# REF_Base.net
KiCad netlist of a schematic drawn in EasyEDA Pro
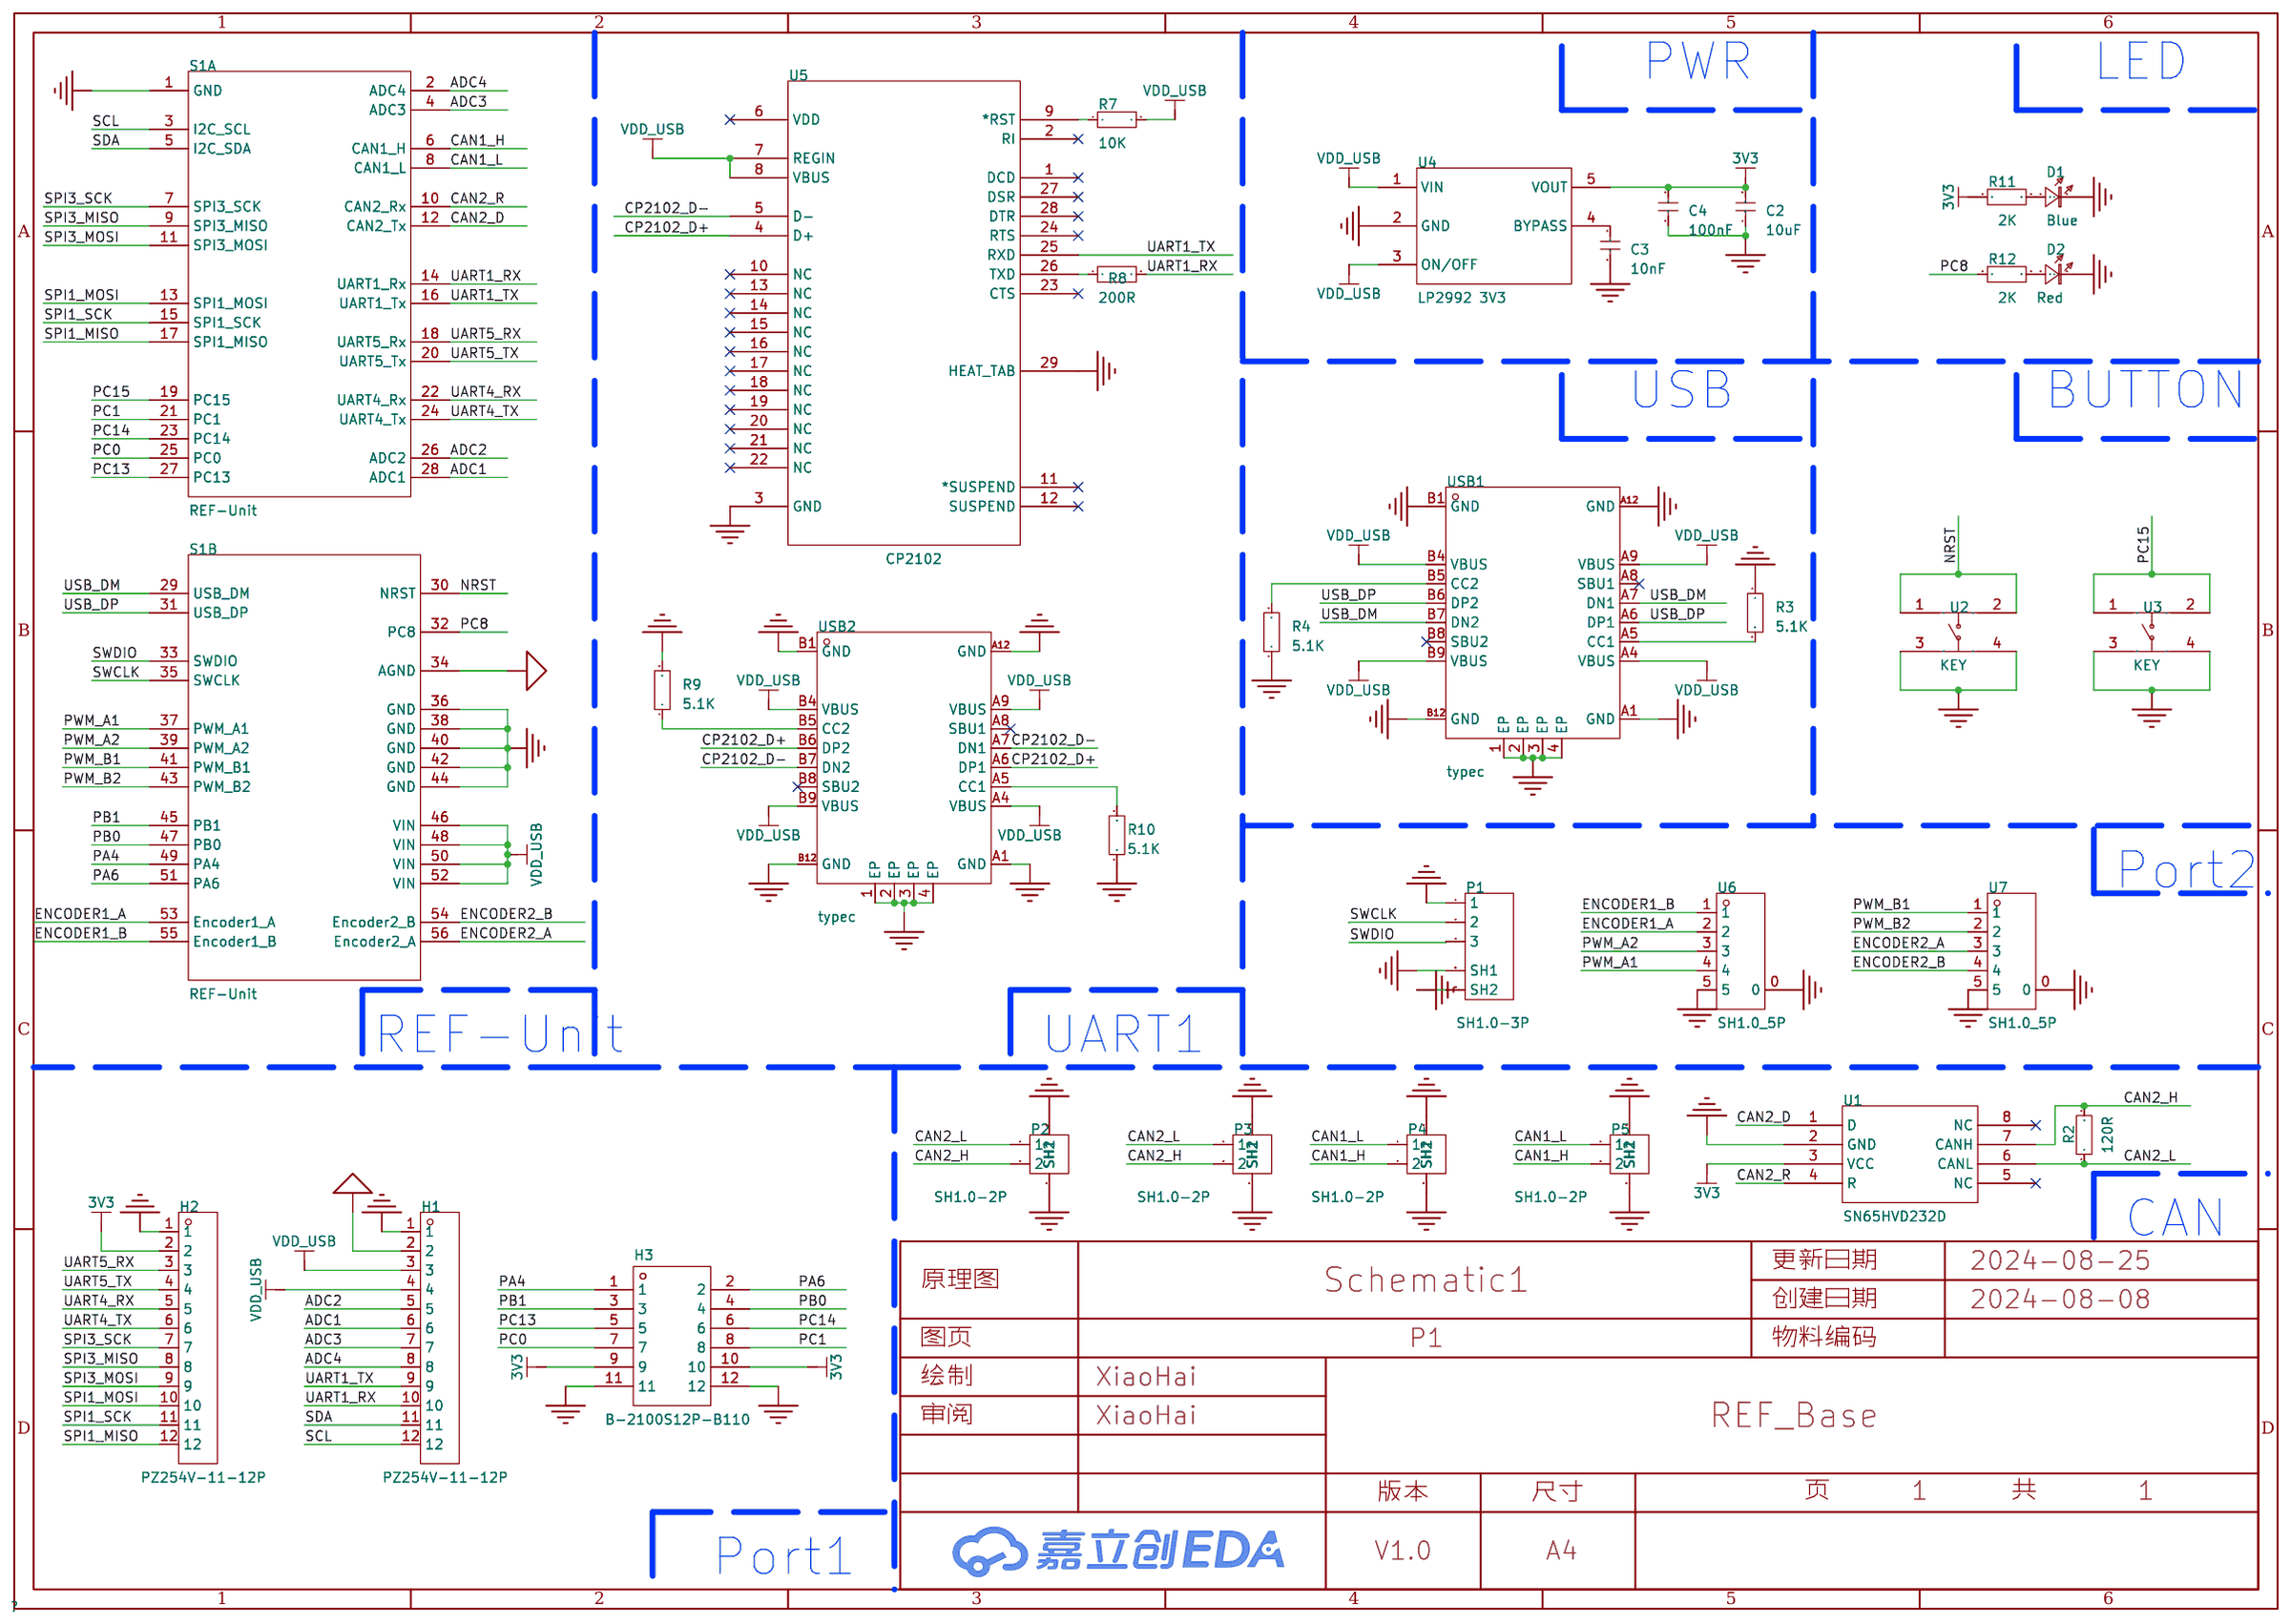
[diagram p0: schematic sheet]

(export (version "E")
  (design (tool "Eeschema 10.0.6"))
  (components
    (comp (ref "C2")
      (value "0.1u")
      (footprint "easyedapro:CAP_0402")
      (libsource (lib "easyedapro") (part "电容-0402"))
    )
    (comp (ref "C3")
      (value "0.1u")
      (footprint "easyedapro:CAP_0402")
      (libsource (lib "easyedapro") (part "电容-0402"))
    )
    (comp (ref "C4")
      (value "0.1u")
      (footprint "easyedapro:CAP_0402")
      (libsource (lib "easyedapro") (part "电容-0402"))
    )
    (comp (ref "D1")
      (value "color?")
      (footprint "easyedapro:LED_0402_RED")
      (libsource (lib "easyedapro") (part "LED_0402"))
    )
    (comp (ref "D2")
      (value "color?")
      (footprint "easyedapro:LED_0402_RED")
      (libsource (lib "easyedapro") (part "LED_0402"))
    )
    (comp (ref "H1")
      (value "PZ254V-11-12P")
      (footprint "easyedapro:HDR-TH_12P-P2.54-V-M")
      (fields (field (name "Manufacturer") "XFCN(兴飞)"))
      (libsource (lib "easyedapro") (part "PZ254V-11-12P"))
    )
    (comp (ref "H2")
      (value "PZ254V-11-12P")
      (footprint "easyedapro:HDR-TH_12P-P2.54-V-M")
      (fields (field (name "Manufacturer") "XFCN(兴飞)"))
      (libsource (lib "easyedapro") (part "PZ254V-11-12P"))
    )
    (comp (ref "H3")
      (value "B-2100S12P-B110")
      (footprint "easyedapro:HDR-TH_12P-P2.54-V-M-R2-C6-S2.54")
      (fields (field (name "Manufacturer") "Ckmtw(灿科盟)"))
      (libsource (lib "easyedapro") (part "210S-2*6P L=11.6MMGold-plated black"))
    )
    (comp (ref "P1")
      (value "SH1.0-3P")
      (footprint "easyedapro:SH1.0-3P")
      (libsource (lib "easyedapro") (part "SH1.0-3P"))
    )
    (comp (ref "P2")
      (value "SH1.0-2P")
      (footprint "easyedapro:SH1.0-2P")
      (libsource (lib "easyedapro") (part "SH1.0-2P"))
    )
    (comp (ref "P3")
      (value "SH1.0-2P")
      (footprint "easyedapro:SH1.0-2P")
      (libsource (lib "easyedapro") (part "SH1.0-2P"))
    )
    (comp (ref "P4")
      (value "SH1.0-2P")
      (footprint "easyedapro:SH1.0-2P")
      (libsource (lib "easyedapro") (part "SH1.0-2P"))
    )
    (comp (ref "P5")
      (value "SH1.0-2P")
      (footprint "easyedapro:SH1.0-2P")
      (libsource (lib "easyedapro") (part "SH1.0-2P"))
    )
    (comp (ref "R2")
      (value "22R")
      (footprint "easyedapro:RES_0402")
      (libsource (lib "easyedapro") (part "电阻-0402"))
    )
    (comp (ref "R3")
      (value "22R")
      (footprint "easyedapro:RES_0402")
      (libsource (lib "easyedapro") (part "电阻-0402"))
    )
    (comp (ref "R4")
      (value "22R")
      (footprint "easyedapro:RES_0402")
      (libsource (lib "easyedapro") (part "电阻-0402"))
    )
    (comp (ref "R7")
      (value "22R")
      (footprint "easyedapro:RES_0402")
      (libsource (lib "easyedapro") (part "电阻-0402"))
    )
    (comp (ref "R8")
      (value "22R")
      (footprint "easyedapro:RES_0402")
      (libsource (lib "easyedapro") (part "电阻-0402"))
    )
    (comp (ref "R9")
      (value "22R")
      (footprint "easyedapro:RES_0402")
      (libsource (lib "easyedapro") (part "电阻-0402"))
    )
    (comp (ref "R10")
      (value "22R")
      (footprint "easyedapro:RES_0402")
      (libsource (lib "easyedapro") (part "电阻-0402"))
    )
    (comp (ref "R11")
      (value "22R")
      (footprint "easyedapro:RES_0402")
      (libsource (lib "easyedapro") (part "电阻-0402"))
    )
    (comp (ref "R12")
      (value "22R")
      (footprint "easyedapro:RES_0402")
      (libsource (lib "easyedapro") (part "电阻-0402"))
    )
    (comp (ref "S1")
      (value "REF-Unit")
      (footprint "easyedapro:REF-UNIT")
      (libsource (lib "easyedapro") (part "REF-Unit"))
    )
    (comp (ref "U1")
      (value "SN65HVD232D")
      (footprint "easyedapro:SO-8")
      (fields (field (name "Manufacturer") "Texas Instruments"))
      (libsource (lib "easyedapro") (part "SN65HVD232D"))
    )
    (comp (ref "U2")
      (value "KEY")
      (footprint "easyedapro:KEY-SMD_TSC4A")
      (fields (field (name "Manufacturer") "SHOU HAN(首韩)"))
      (libsource (lib "easyedapro") (part "TSC4A 160GF-WZ 016"))
    )
    (comp (ref "U3")
      (value "KEY")
      (footprint "easyedapro:KEY-SMD_TSC4A")
      (fields (field (name "Manufacturer") "SHOU HAN(首韩)"))
      (libsource (lib "easyedapro") (part "TSC4A 160GF-WZ 016"))
    )
    (comp (ref "U4")
      (value "LP2992 3V3")
      (footprint "easyedapro:SOT23-5")
      (libsource (lib "easyedapro") (part "LP2992"))
    )
    (comp (ref "U5")
      (value "Value")
      (footprint "easyedapro:QFN-28")
      (libsource (lib "easyedapro") (part "CP2102"))
    )
    (comp (ref "U6")
      (value "SH1.0_5P")
      (footprint "easyedapro:CONN-SMD_5P-SH1.00-5P-WT")
      (libsource (lib "easyedapro") (part "SH1.0_5P"))
    )
    (comp (ref "U7")
      (value "SH1.0_5P")
      (footprint "easyedapro:CONN-SMD_5P-SH1.00-5P-WT")
      (libsource (lib "easyedapro") (part "SH1.0_5P"))
    )
    (comp (ref "USB1")
      (value "typec")
      (footprint "easyedapro:USB-C-SMD_KH-TYPE-C-16P")
      (libsource (lib "easyedapro") (part "TYPEC_C9900016956"))
    )
    (comp (ref "USB2")
      (value "typec")
      (footprint "easyedapro:USB-C-SMD_KH-TYPE-C-16P")
      (libsource (lib "easyedapro") (part "TYPEC_C9900016956"))
    )
  )
  (nets
    (net (code "1") (name "/ADC1") (class "Default")
      (node (ref "H1") (pin "6") (pinfunction "6_6") (pintype "unspecified"))
      (node (ref "S1") (pin "28") (pinfunction "ADC1_28") (pintype "input"))
    )
    (net (code "2") (name "/ADC2") (class "Default")
      (node (ref "H1") (pin "5") (pinfunction "5_5") (pintype "unspecified"))
      (node (ref "S1") (pin "26") (pinfunction "ADC2_26") (pintype "input"))
    )
    (net (code "3") (name "/ADC3") (class "Default")
      (node (ref "H1") (pin "7") (pinfunction "7_7") (pintype "unspecified"))
      (node (ref "S1") (pin "4") (pinfunction "ADC3_4") (pintype "input"))
    )
    (net (code "4") (name "/ADC4") (class "Default")
      (node (ref "H1") (pin "8") (pinfunction "8_8") (pintype "unspecified"))
      (node (ref "S1") (pin "2") (pinfunction "ADC4_2") (pintype "input"))
    )
    (net (code "5") (name "/CAN1_H") (class "Default")
      (node (ref "P4") (pin "2") (pinfunction "2_2") (pintype "unspecified"))
      (node (ref "P5") (pin "2") (pinfunction "2_2") (pintype "unspecified"))
      (node (ref "S1") (pin "6") (pinfunction "CAN1_H_6") (pintype "bidirectional"))
    )
    (net (code "6") (name "/CAN1_L") (class "Default")
      (node (ref "P4") (pin "1") (pinfunction "1_1") (pintype "unspecified"))
      (node (ref "P5") (pin "1") (pinfunction "1_1") (pintype "unspecified"))
      (node (ref "S1") (pin "8") (pinfunction "CAN1_L_8") (pintype "bidirectional"))
    )
    (net (code "7") (name "/CAN2_D") (class "Default")
      (node (ref "S1") (pin "12") (pinfunction "CAN2_Tx_12") (pintype "bidirectional"))
      (node (ref "U1") (pin "1") (pinfunction "D_1") (pintype "unspecified"))
    )
    (net (code "8") (name "/CAN2_H") (class "Default")
      (node (ref "P2") (pin "2") (pinfunction "2_2") (pintype "unspecified"))
      (node (ref "P3") (pin "2") (pinfunction "2_2") (pintype "unspecified"))
      (node (ref "R2") (pin "2") (pinfunction "2_2") (pintype "unspecified"))
      (node (ref "U1") (pin "7") (pinfunction "CANH_7") (pintype "unspecified"))
    )
    (net (code "9") (name "/CAN2_L") (class "Default")
      (node (ref "P2") (pin "1") (pinfunction "1_1") (pintype "unspecified"))
      (node (ref "P3") (pin "1") (pinfunction "1_1") (pintype "unspecified"))
      (node (ref "R2") (pin "1") (pinfunction "1_1") (pintype "unspecified"))
      (node (ref "U1") (pin "6") (pinfunction "CANL_6") (pintype "unspecified"))
    )
    (net (code "10") (name "/CAN2_R") (class "Default")
      (node (ref "S1") (pin "10") (pinfunction "CAN2_Rx_10") (pintype "bidirectional"))
      (node (ref "U1") (pin "4") (pinfunction "R_4") (pintype "unspecified"))
    )
    (net (code "11") (name "/CP2102_D+") (class "Default")
      (node (ref "U5") (pin "4") (pinfunction "D+_4") (pintype "unspecified"))
      (node (ref "USB2") (pin "A6") (pinfunction "DP1_A6") (pintype "unspecified"))
      (node (ref "USB2") (pin "B6") (pinfunction "DP2_B6") (pintype "unspecified"))
    )
    (net (code "12") (name "/CP2102_D-") (class "Default")
      (node (ref "U5") (pin "5") (pinfunction "D-_5") (pintype "unspecified"))
      (node (ref "USB2") (pin "A7") (pinfunction "DN1_A7") (pintype "unspecified"))
      (node (ref "USB2") (pin "B7") (pinfunction "DN2_B7") (pintype "unspecified"))
    )
    (net (code "13") (name "/ENCODER1_A") (class "Default")
      (node (ref "S1") (pin "53") (pinfunction "Encoder1_A_53") (pintype "input"))
      (node (ref "U6") (pin "2") (pinfunction "2_2") (pintype "unspecified"))
    )
    (net (code "14") (name "/ENCODER1_B") (class "Default")
      (node (ref "S1") (pin "55") (pinfunction "Encoder1_B_55") (pintype "input"))
      (node (ref "U6") (pin "1") (pinfunction "1_1") (pintype "unspecified"))
    )
    (net (code "15") (name "/ENCODER2_A") (class "Default")
      (node (ref "S1") (pin "56") (pinfunction "Encoder2_A_56") (pintype "input"))
      (node (ref "U7") (pin "3") (pinfunction "3_3") (pintype "unspecified"))
    )
    (net (code "16") (name "/ENCODER2_B") (class "Default")
      (node (ref "S1") (pin "54") (pinfunction "Encoder2_B_54") (pintype "input"))
      (node (ref "U7") (pin "4") (pinfunction "4_4") (pintype "unspecified"))
    )
    (net (code "17") (name "/NRST") (class "Default")
      (node (ref "S1") (pin "30") (pinfunction "NRST_30") (pintype "unspecified"))
      (node (ref "U2") (pin "1") (pinfunction "1_1") (pintype "unspecified"))
      (node (ref "U2") (pin "2") (pinfunction "2_2") (pintype "unspecified"))
    )
    (net (code "18") (name "/PA4") (class "Default")
      (node (ref "H3") (pin "1") (pinfunction "1_1") (pintype "unspecified"))
      (node (ref "S1") (pin "49") (pinfunction "PA4_49") (pintype "bidirectional"))
    )
    (net (code "19") (name "/PA6") (class "Default")
      (node (ref "H3") (pin "2") (pinfunction "2_2") (pintype "unspecified"))
      (node (ref "S1") (pin "51") (pinfunction "PA6_51") (pintype "bidirectional"))
    )
    (net (code "20") (name "/PB0") (class "Default")
      (node (ref "H3") (pin "4") (pinfunction "4_4") (pintype "unspecified"))
      (node (ref "S1") (pin "47") (pinfunction "PB0_47") (pintype "bidirectional"))
    )
    (net (code "21") (name "/PB1") (class "Default")
      (node (ref "H3") (pin "3") (pinfunction "3_3") (pintype "unspecified"))
      (node (ref "S1") (pin "45") (pinfunction "PB1_45") (pintype "bidirectional"))
    )
    (net (code "22") (name "/PC0") (class "Default")
      (node (ref "H3") (pin "7") (pinfunction "7_7") (pintype "unspecified"))
      (node (ref "S1") (pin "25") (pinfunction "PC0_25") (pintype "bidirectional"))
    )
    (net (code "23") (name "/PC1") (class "Default")
      (node (ref "H3") (pin "8") (pinfunction "8_8") (pintype "unspecified"))
      (node (ref "S1") (pin "21") (pinfunction "PC1_21") (pintype "bidirectional"))
    )
    (net (code "24") (name "/PC8") (class "Default")
      (node (ref "R12") (pin "1") (pinfunction "1_1") (pintype "unspecified"))
      (node (ref "S1") (pin "32") (pinfunction "PC8_32") (pintype "bidirectional"))
    )
    (net (code "25") (name "/PC13") (class "Default")
      (node (ref "H3") (pin "5") (pinfunction "5_5") (pintype "unspecified"))
      (node (ref "S1") (pin "27") (pinfunction "PC13_27") (pintype "bidirectional"))
    )
    (net (code "26") (name "/PC14") (class "Default")
      (node (ref "H3") (pin "6") (pinfunction "6_6") (pintype "unspecified"))
      (node (ref "S1") (pin "23") (pinfunction "PC14_23") (pintype "bidirectional"))
    )
    (net (code "27") (name "/PC15") (class "Default")
      (node (ref "S1") (pin "19") (pinfunction "PC15_19") (pintype "bidirectional"))
      (node (ref "U3") (pin "1") (pinfunction "1_1") (pintype "unspecified"))
      (node (ref "U3") (pin "2") (pinfunction "2_2") (pintype "unspecified"))
    )
    (net (code "28") (name "/PWM_A1") (class "Default")
      (node (ref "S1") (pin "37") (pinfunction "PWM_A1_37") (pintype "output"))
      (node (ref "U6") (pin "4") (pinfunction "4_4") (pintype "unspecified"))
    )
    (net (code "29") (name "/PWM_A2") (class "Default")
      (node (ref "S1") (pin "39") (pinfunction "PWM_A2_39") (pintype "output"))
      (node (ref "U6") (pin "3") (pinfunction "3_3") (pintype "unspecified"))
    )
    (net (code "30") (name "/PWM_B1") (class "Default")
      (node (ref "S1") (pin "41") (pinfunction "PWM_B1_41") (pintype "output"))
      (node (ref "U7") (pin "1") (pinfunction "1_1") (pintype "unspecified"))
    )
    (net (code "31") (name "/PWM_B2") (class "Default")
      (node (ref "S1") (pin "43") (pinfunction "PWM_B2_43") (pintype "output"))
      (node (ref "U7") (pin "2") (pinfunction "2_2") (pintype "unspecified"))
    )
    (net (code "32") (name "/SCL") (class "Default")
      (node (ref "H1") (pin "12") (pinfunction "12_12") (pintype "unspecified"))
      (node (ref "S1") (pin "3") (pinfunction "I2C_SCL_3") (pintype "bidirectional"))
    )
    (net (code "33") (name "/SDA") (class "Default")
      (node (ref "H1") (pin "11") (pinfunction "11_11") (pintype "unspecified"))
      (node (ref "S1") (pin "5") (pinfunction "I2C_SDA_5") (pintype "bidirectional"))
    )
    (net (code "34") (name "/SPI1_MISO") (class "Default")
      (node (ref "H2") (pin "12") (pinfunction "12_12") (pintype "unspecified"))
      (node (ref "S1") (pin "17") (pinfunction "SPI1_MISO_17") (pintype "bidirectional"))
    )
    (net (code "35") (name "/SPI1_MOSI") (class "Default")
      (node (ref "H2") (pin "10") (pinfunction "10_10") (pintype "unspecified"))
      (node (ref "S1") (pin "13") (pinfunction "SPI1_MOSI_13") (pintype "bidirectional"))
    )
    (net (code "36") (name "/SPI1_SCK") (class "Default")
      (node (ref "H2") (pin "11") (pinfunction "11_11") (pintype "unspecified"))
      (node (ref "S1") (pin "15") (pinfunction "SPI1_SCK_15") (pintype "bidirectional"))
    )
    (net (code "37") (name "/SPI3_MISO") (class "Default")
      (node (ref "H2") (pin "8") (pinfunction "8_8") (pintype "unspecified"))
      (node (ref "S1") (pin "9") (pinfunction "SPI3_MISO_9") (pintype "bidirectional"))
    )
    (net (code "38") (name "/SPI3_MOSI") (class "Default")
      (node (ref "H2") (pin "9") (pinfunction "9_9") (pintype "unspecified"))
      (node (ref "S1") (pin "11") (pinfunction "SPI3_MOSI_11") (pintype "bidirectional"))
    )
    (net (code "39") (name "/SPI3_SCK") (class "Default")
      (node (ref "H2") (pin "7") (pinfunction "7_7") (pintype "unspecified"))
      (node (ref "S1") (pin "7") (pinfunction "SPI3_SCK_7") (pintype "bidirectional"))
    )
    (net (code "40") (name "/SWCLK") (class "Default")
      (node (ref "P1") (pin "2") (pinfunction "2_2") (pintype "unspecified"))
      (node (ref "S1") (pin "35") (pinfunction "SWCLK_35") (pintype "bidirectional"))
    )
    (net (code "41") (name "/SWDIO") (class "Default")
      (node (ref "P1") (pin "3") (pinfunction "3_3") (pintype "unspecified"))
      (node (ref "S1") (pin "33") (pinfunction "SWDIO_33") (pintype "bidirectional"))
    )
    (net (code "42") (name "/UART1_RX") (class "Default")
      (node (ref "H1") (pin "10") (pinfunction "10_10") (pintype "unspecified"))
      (node (ref "R8") (pin "2") (pinfunction "2_2") (pintype "unspecified"))
      (node (ref "S1") (pin "14") (pinfunction "UART1_Rx_14") (pintype "bidirectional"))
    )
    (net (code "43") (name "/UART1_TX") (class "Default")
      (node (ref "H1") (pin "9") (pinfunction "9_9") (pintype "unspecified"))
      (node (ref "S1") (pin "16") (pinfunction "UART1_Tx_16") (pintype "bidirectional"))
      (node (ref "U5") (pin "25") (pinfunction "RXD_25") (pintype "unspecified"))
    )
    (net (code "44") (name "/UART4_RX") (class "Default")
      (node (ref "H2") (pin "5") (pinfunction "5_5") (pintype "unspecified"))
      (node (ref "S1") (pin "22") (pinfunction "UART4_Rx_22") (pintype "bidirectional"))
    )
    (net (code "45") (name "/UART4_TX") (class "Default")
      (node (ref "H2") (pin "6") (pinfunction "6_6") (pintype "unspecified"))
      (node (ref "S1") (pin "24") (pinfunction "UART4_Tx_24") (pintype "bidirectional"))
    )
    (net (code "46") (name "/UART5_RX") (class "Default")
      (node (ref "H2") (pin "3") (pinfunction "3_3") (pintype "unspecified"))
      (node (ref "S1") (pin "18") (pinfunction "UART5_Rx_18") (pintype "bidirectional"))
    )
    (net (code "47") (name "/UART5_TX") (class "Default")
      (node (ref "H2") (pin "4") (pinfunction "4_4") (pintype "unspecified"))
      (node (ref "S1") (pin "20") (pinfunction "UART5_Tx_20") (pintype "bidirectional"))
    )
    (net (code "48") (name "/USB_DM") (class "Default")
      (node (ref "S1") (pin "29") (pinfunction "USB_DM_29") (pintype "bidirectional"))
      (node (ref "USB1") (pin "A7") (pinfunction "DN1_A7") (pintype "unspecified"))
      (node (ref "USB1") (pin "B7") (pinfunction "DN2_B7") (pintype "unspecified"))
    )
    (net (code "49") (name "/USB_DP") (class "Default")
      (node (ref "S1") (pin "31") (pinfunction "USB_DP_31") (pintype "bidirectional"))
      (node (ref "USB1") (pin "A6") (pinfunction "DP1_A6") (pintype "unspecified"))
      (node (ref "USB1") (pin "B6") (pinfunction "DP2_B6") (pintype "unspecified"))
    )
    (net (code "50") (name "3V3") (class "Default")
      (node (ref "C2") (pin "2") (pinfunction "2_2") (pintype "unspecified"))
      (node (ref "C4") (pin "1") (pinfunction "1_1") (pintype "unspecified"))
      (node (ref "H2") (pin "2") (pinfunction "2_2") (pintype "unspecified"))
      (node (ref "H3") (pin "10") (pinfunction "10_10") (pintype "unspecified"))
      (node (ref "H3") (pin "9") (pinfunction "9_9") (pintype "unspecified"))
      (node (ref "R11") (pin "1") (pinfunction "1_1") (pintype "unspecified"))
      (node (ref "U1") (pin "3") (pinfunction "VCC_3") (pintype "unspecified"))
      (node (ref "U4") (pin "5") (pinfunction "VOUT_5") (pintype "unspecified"))
    )
    (net (code "51") (name "AGND") (class "Default")
      (node (ref "H1") (pin "2") (pinfunction "2_2") (pintype "unspecified"))
      (node (ref "S1") (pin "34") (pinfunction "AGND_34") (pintype "unspecified"))
    )
    (net (code "52") (name "GND") (class "Default")
      (node (ref "C2") (pin "1") (pinfunction "1_1") (pintype "unspecified"))
      (node (ref "C3") (pin "1") (pinfunction "1_1") (pintype "unspecified"))
      (node (ref "C4") (pin "2") (pinfunction "2_2") (pintype "unspecified"))
      (node (ref "D1") (pin "2") (pinfunction "K_2") (pintype "unspecified"))
      (node (ref "D2") (pin "2") (pinfunction "K_2") (pintype "unspecified"))
      (node (ref "H1") (pin "1") (pinfunction "1_1") (pintype "unspecified"))
      (node (ref "H2") (pin "1") (pinfunction "1_1") (pintype "unspecified"))
      (node (ref "H3") (pin "11") (pinfunction "11_11") (pintype "unspecified"))
      (node (ref "H3") (pin "12") (pinfunction "12_12") (pintype "unspecified"))
      (node (ref "P1") (pin "1") (pinfunction "1_1") (pintype "unspecified"))
      (node (ref "P1") (pin "SH1") (pinfunction "SH1_SH1") (pintype "unspecified"))
      (node (ref "P1") (pin "SH2") (pinfunction "SH2_SH2") (pintype "unspecified"))
      (node (ref "P2") (pin "SH1") (pinfunction "SH1_SH1") (pintype "unspecified"))
      (node (ref "P2") (pin "SH2") (pinfunction "SH2_SH2") (pintype "unspecified"))
      (node (ref "P3") (pin "SH1") (pinfunction "SH1_SH1") (pintype "unspecified"))
      (node (ref "P3") (pin "SH2") (pinfunction "SH2_SH2") (pintype "unspecified"))
      (node (ref "P4") (pin "SH1") (pinfunction "SH1_SH1") (pintype "unspecified"))
      (node (ref "P4") (pin "SH2") (pinfunction "SH2_SH2") (pintype "unspecified"))
      (node (ref "P5") (pin "SH1") (pinfunction "SH1_SH1") (pintype "unspecified"))
      (node (ref "P5") (pin "SH2") (pinfunction "SH2_SH2") (pintype "unspecified"))
      (node (ref "R10") (pin "1") (pinfunction "1_1") (pintype "unspecified"))
      (node (ref "R3") (pin "1") (pinfunction "1_1") (pintype "unspecified"))
      (node (ref "R4") (pin "1") (pinfunction "1_1") (pintype "unspecified"))
      (node (ref "R9") (pin "2") (pinfunction "2_2") (pintype "unspecified"))
      (node (ref "S1") (pin "1") (pinfunction "GND_1") (pintype "unspecified"))
      (node (ref "S1") (pin "36") (pinfunction "GND_36") (pintype "unspecified"))
      (node (ref "S1") (pin "38") (pinfunction "GND_38") (pintype "unspecified"))
      (node (ref "S1") (pin "40") (pinfunction "GND_40") (pintype "unspecified"))
      (node (ref "S1") (pin "42") (pinfunction "GND_42") (pintype "unspecified"))
      (node (ref "S1") (pin "44") (pinfunction "GND_44") (pintype "unspecified"))
      (node (ref "U1") (pin "2") (pinfunction "GND_2") (pintype "unspecified"))
      (node (ref "U2") (pin "3") (pinfunction "3_3") (pintype "unspecified"))
      (node (ref "U2") (pin "4") (pinfunction "4_4") (pintype "unspecified"))
      (node (ref "U3") (pin "3") (pinfunction "3_3") (pintype "unspecified"))
      (node (ref "U3") (pin "4") (pinfunction "4_4") (pintype "unspecified"))
      (node (ref "U4") (pin "2") (pinfunction "GND_2") (pintype "unspecified"))
      (node (ref "U5") (pin "29") (pinfunction "HEAT_TAB_29") (pintype "unspecified"))
      (node (ref "U5") (pin "3") (pinfunction "GND_3") (pintype "unspecified"))
      (node (ref "U6") (pin "0") (pinfunction "0_0") (pintype "unspecified"))
      (node (ref "U6") (pin "5") (pinfunction "5_5") (pintype "unspecified"))
      (node (ref "U7") (pin "0") (pinfunction "0_0") (pintype "unspecified"))
      (node (ref "U7") (pin "5") (pinfunction "5_5") (pintype "unspecified"))
      (node (ref "USB1") (pin "1") (pinfunction "EP_1") (pintype "unspecified"))
      (node (ref "USB1") (pin "2") (pinfunction "EP_2") (pintype "unspecified"))
      (node (ref "USB1") (pin "3") (pinfunction "EP_3") (pintype "unspecified"))
      (node (ref "USB1") (pin "4") (pinfunction "EP_4") (pintype "unspecified"))
      (node (ref "USB1") (pin "A1") (pinfunction "GND_A1") (pintype "unspecified"))
      (node (ref "USB1") (pin "A12") (pinfunction "GND_A12") (pintype "unspecified"))
      (node (ref "USB1") (pin "B1") (pinfunction "GND_B1") (pintype "unspecified"))
      (node (ref "USB1") (pin "B12") (pinfunction "GND_B12") (pintype "unspecified"))
      (node (ref "USB2") (pin "1") (pinfunction "EP_1") (pintype "unspecified"))
      (node (ref "USB2") (pin "2") (pinfunction "EP_2") (pintype "unspecified"))
      (node (ref "USB2") (pin "3") (pinfunction "EP_3") (pintype "unspecified"))
      (node (ref "USB2") (pin "4") (pinfunction "EP_4") (pintype "unspecified"))
      (node (ref "USB2") (pin "A1") (pinfunction "GND_A1") (pintype "unspecified"))
      (node (ref "USB2") (pin "A12") (pinfunction "GND_A12") (pintype "unspecified"))
      (node (ref "USB2") (pin "B1") (pinfunction "GND_B1") (pintype "unspecified"))
      (node (ref "USB2") (pin "B12") (pinfunction "GND_B12") (pintype "unspecified"))
    )
    (net (code "53") (name "Net-(D1-A)") (class "Default")
      (node (ref "D1") (pin "1") (pinfunction "A_1") (pintype "unspecified"))
      (node (ref "R11") (pin "2") (pinfunction "2_2") (pintype "unspecified"))
    )
    (net (code "54") (name "Net-(D2-A)") (class "Default")
      (node (ref "D2") (pin "1") (pinfunction "A_1") (pintype "unspecified"))
      (node (ref "R12") (pin "2") (pinfunction "2_2") (pintype "unspecified"))
    )
    (net (code "55") (name "Net-(U4-BYPASS)") (class "Default")
      (node (ref "C3") (pin "2") (pinfunction "2_2") (pintype "unspecified"))
      (node (ref "U4") (pin "4") (pinfunction "BYPASS_4") (pintype "unspecified"))
    )
    (net (code "56") (name "Net-(U5-*RST)") (class "Default")
      (node (ref "R7") (pin "1") (pinfunction "1_1") (pintype "unspecified"))
      (node (ref "U5") (pin "9") (pinfunction "*RST_9") (pintype "unspecified"))
    )
    (net (code "57") (name "Net-(U5-TXD)") (class "Default")
      (node (ref "R8") (pin "1") (pinfunction "1_1") (pintype "unspecified"))
      (node (ref "U5") (pin "26") (pinfunction "TXD_26") (pintype "unspecified"))
    )
    (net (code "58") (name "Net-(USB1-CC1)") (class "Default")
      (node (ref "R3") (pin "2") (pinfunction "2_2") (pintype "unspecified"))
      (node (ref "USB1") (pin "A5") (pinfunction "CC1_A5") (pintype "unspecified"))
    )
    (net (code "59") (name "Net-(USB1-CC2)") (class "Default")
      (node (ref "R4") (pin "2") (pinfunction "2_2") (pintype "unspecified"))
      (node (ref "USB1") (pin "B5") (pinfunction "CC2_B5") (pintype "unspecified"))
    )
    (net (code "60") (name "Net-(USB2-CC1)") (class "Default")
      (node (ref "R10") (pin "2") (pinfunction "2_2") (pintype "unspecified"))
      (node (ref "USB2") (pin "A5") (pinfunction "CC1_A5") (pintype "unspecified"))
    )
    (net (code "61") (name "Net-(USB2-CC2)") (class "Default")
      (node (ref "R9") (pin "1") (pinfunction "1_1") (pintype "unspecified"))
      (node (ref "USB2") (pin "B5") (pinfunction "CC2_B5") (pintype "unspecified"))
    )
    (net (code "62") (name "VDD_USB") (class "Default")
      (node (ref "H1") (pin "3") (pinfunction "3_3") (pintype "unspecified"))
      (node (ref "H1") (pin "4") (pinfunction "4_4") (pintype "unspecified"))
      (node (ref "R7") (pin "2") (pinfunction "2_2") (pintype "unspecified"))
      (node (ref "S1") (pin "46") (pinfunction "VIN_46") (pintype "unspecified"))
      (node (ref "S1") (pin "48") (pinfunction "VIN_48") (pintype "unspecified"))
      (node (ref "S1") (pin "50") (pinfunction "VIN_50") (pintype "unspecified"))
      (node (ref "S1") (pin "52") (pinfunction "VIN_52") (pintype "unspecified"))
      (node (ref "U4") (pin "1") (pinfunction "VIN_1") (pintype "unspecified"))
      (node (ref "U4") (pin "3") (pinfunction "ON/OFF_3") (pintype "unspecified"))
      (node (ref "U5") (pin "7") (pinfunction "REGIN_7") (pintype "unspecified"))
      (node (ref "U5") (pin "8") (pinfunction "VBUS_8") (pintype "unspecified"))
      (node (ref "USB1") (pin "A4") (pinfunction "VBUS_A4") (pintype "unspecified"))
      (node (ref "USB1") (pin "A9") (pinfunction "VBUS_A9") (pintype "unspecified"))
      (node (ref "USB1") (pin "B4") (pinfunction "VBUS_B4") (pintype "unspecified"))
      (node (ref "USB1") (pin "B9") (pinfunction "VBUS_B9") (pintype "unspecified"))
      (node (ref "USB2") (pin "A4") (pinfunction "VBUS_A4") (pintype "unspecified"))
      (node (ref "USB2") (pin "A9") (pinfunction "VBUS_A9") (pintype "unspecified"))
      (node (ref "USB2") (pin "B4") (pinfunction "VBUS_B4") (pintype "unspecified"))
      (node (ref "USB2") (pin "B9") (pinfunction "VBUS_B9") (pintype "unspecified"))
    )
    (net (code "63") (name "unconnected-(U1-NC-Pad5)") (class "Default")
      (node (ref "U1") (pin "5") (pinfunction "NC_5") (pintype "unspecified+no_connect"))
    )
    (net (code "64") (name "unconnected-(U1-NC-Pad8)") (class "Default")
      (node (ref "U1") (pin "8") (pinfunction "NC_8") (pintype "unspecified+no_connect"))
    )
    (net (code "65") (name "unconnected-(U5-*SUSPEND-Pad11)") (class "Default")
      (node (ref "U5") (pin "11") (pinfunction "*SUSPEND_11") (pintype "unspecified+no_connect"))
    )
    (net (code "66") (name "unconnected-(U5-CTS-Pad23)") (class "Default")
      (node (ref "U5") (pin "23") (pinfunction "CTS_23") (pintype "unspecified+no_connect"))
    )
    (net (code "67") (name "unconnected-(U5-DCD-Pad1)") (class "Default")
      (node (ref "U5") (pin "1") (pinfunction "DCD_1") (pintype "unspecified+no_connect"))
    )
    (net (code "68") (name "unconnected-(U5-DSR-Pad27)") (class "Default")
      (node (ref "U5") (pin "27") (pinfunction "DSR_27") (pintype "unspecified+no_connect"))
    )
    (net (code "69") (name "unconnected-(U5-DTR-Pad28)") (class "Default")
      (node (ref "U5") (pin "28") (pinfunction "DTR_28") (pintype "unspecified+no_connect"))
    )
    (net (code "70") (name "unconnected-(U5-NC-Pad10)") (class "Default")
      (node (ref "U5") (pin "10") (pinfunction "NC_10") (pintype "unspecified+no_connect"))
    )
    (net (code "71") (name "unconnected-(U5-NC-Pad13)") (class "Default")
      (node (ref "U5") (pin "13") (pinfunction "NC_13") (pintype "unspecified+no_connect"))
    )
    (net (code "72") (name "unconnected-(U5-NC-Pad14)") (class "Default")
      (node (ref "U5") (pin "14") (pinfunction "NC_14") (pintype "unspecified+no_connect"))
    )
    (net (code "73") (name "unconnected-(U5-NC-Pad15)") (class "Default")
      (node (ref "U5") (pin "15") (pinfunction "NC_15") (pintype "unspecified+no_connect"))
    )
    (net (code "74") (name "unconnected-(U5-NC-Pad16)") (class "Default")
      (node (ref "U5") (pin "16") (pinfunction "NC_16") (pintype "unspecified+no_connect"))
    )
    (net (code "75") (name "unconnected-(U5-NC-Pad17)") (class "Default")
      (node (ref "U5") (pin "17") (pinfunction "NC_17") (pintype "unspecified+no_connect"))
    )
    (net (code "76") (name "unconnected-(U5-NC-Pad18)") (class "Default")
      (node (ref "U5") (pin "18") (pinfunction "NC_18") (pintype "unspecified+no_connect"))
    )
    (net (code "77") (name "unconnected-(U5-NC-Pad19)") (class "Default")
      (node (ref "U5") (pin "19") (pinfunction "NC_19") (pintype "unspecified+no_connect"))
    )
    (net (code "78") (name "unconnected-(U5-NC-Pad20)") (class "Default")
      (node (ref "U5") (pin "20") (pinfunction "NC_20") (pintype "unspecified+no_connect"))
    )
    (net (code "79") (name "unconnected-(U5-NC-Pad21)") (class "Default")
      (node (ref "U5") (pin "21") (pinfunction "NC_21") (pintype "unspecified+no_connect"))
    )
    (net (code "80") (name "unconnected-(U5-NC-Pad22)") (class "Default")
      (node (ref "U5") (pin "22") (pinfunction "NC_22") (pintype "unspecified+no_connect"))
    )
    (net (code "81") (name "unconnected-(U5-RI-Pad2)") (class "Default")
      (node (ref "U5") (pin "2") (pinfunction "RI_2") (pintype "unspecified+no_connect"))
    )
    (net (code "82") (name "unconnected-(U5-RTS-Pad24)") (class "Default")
      (node (ref "U5") (pin "24") (pinfunction "RTS_24") (pintype "unspecified+no_connect"))
    )
    (net (code "83") (name "unconnected-(U5-SUSPEND-Pad12)") (class "Default")
      (node (ref "U5") (pin "12") (pinfunction "SUSPEND_12") (pintype "unspecified+no_connect"))
    )
    (net (code "84") (name "unconnected-(U5-VDD-Pad6)") (class "Default")
      (node (ref "U5") (pin "6") (pinfunction "VDD_6") (pintype "unspecified+no_connect"))
    )
    (net (code "85") (name "unconnected-(USB1-SBU1-PadA8)") (class "Default")
      (node (ref "USB1") (pin "A8") (pinfunction "SBU1_A8") (pintype "unspecified+no_connect"))
    )
    (net (code "86") (name "unconnected-(USB1-SBU2-PadB8)") (class "Default")
      (node (ref "USB1") (pin "B8") (pinfunction "SBU2_B8") (pintype "unspecified+no_connect"))
    )
    (net (code "87") (name "unconnected-(USB2-SBU1-PadA8)") (class "Default")
      (node (ref "USB2") (pin "A8") (pinfunction "SBU1_A8") (pintype "unspecified+no_connect"))
    )
    (net (code "88") (name "unconnected-(USB2-SBU2-PadB8)") (class "Default")
      (node (ref "USB2") (pin "B8") (pinfunction "SBU2_B8") (pintype "unspecified+no_connect"))
    )
  )
)
